# ChargeController.net
KiCad netlist of a schematic drawn in EAGLE
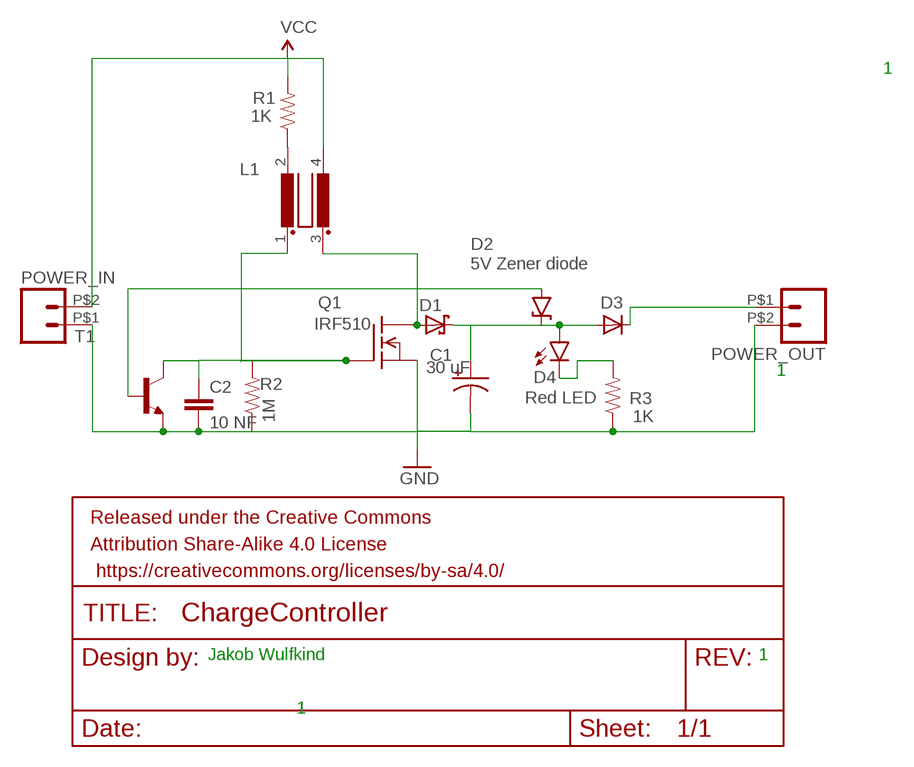
[diagram p0: schematic, sheet 1]

(export (version "E")
  (design (tool "Eeschema 10.0.6"))
  (components
    (comp (ref "C1")
      (value "30 uF")
      (footprint "eagle-import:CPOL-RADIAL-1000UF-25V")
      (libsource (lib "eagle-import") (part "CAP_POLPTH4"))
    )
    (comp (ref "C2")
      (value "10 NF")
      (footprint "eagle-import:CAP-PTH-SMALL-KIT")
      (libsource (lib "eagle-import") (part "0.1UF-50V-20%(PTH)KIT-EZ"))
    )
    (comp (ref "D1")
      (value "SCHOTTKY-DIODEDO201T15")
      (footprint "eagle-import:DO201T15")
      (libsource (lib "eagle-import") (part "SCHOTTKY-DIODEDO201T15"))
    )
    (comp (ref "D2")
      (value "5V Zener diode")
      (footprint "eagle-import:DIODE-ZENER")
      (libsource (lib "eagle-import") (part "DIODE-ZENERPTH"))
    )
    (comp (ref "D3")
      (value "1N5624")
      (footprint "eagle-import:DO201-15")
      (libsource (lib "eagle-import") (part "1N5624"))
    )
    (comp (ref "D4")
      (value "Red LED")
      (footprint "eagle-import:LED3MM")
      (libsource (lib "eagle-import") (part "LED3MM"))
    )
    (comp (ref "FRAME1")
      (value "FRAME-LEDGER")
      (footprint "eagle-import:CREATIVE_COMMONS")
      (libsource (lib "eagle-import") (part "FRAME-LEDGER"))
    )
    (comp (ref "L1")
      (value "R1003XB5")
      (footprint "eagle-import:B5")
      (libsource (lib "eagle-import") (part "R1003XB5"))
    )
    (comp (ref "POWER_IN")
      (value "M02PTH2")
      (footprint "eagle-import:1X02_BIG")
      (libsource (lib "eagle-import") (part "M02PTH2"))
    )
    (comp (ref "POWER_OUT")
      (value "M02PTH2")
      (footprint "eagle-import:1X02_BIG")
      (libsource (lib "eagle-import") (part "M02PTH2"))
    )
    (comp (ref "Q1")
      (value "IRF510")
      (footprint "eagle-import:TO220")
      (libsource (lib "eagle-import") (part "IRF510"))
    )
    (comp (ref "R1")
      (value "1K")
      (footprint "eagle-import:AXIAL-0.4")
      (libsource (lib "eagle-import") (part "RESISTORPTH-1/4W"))
    )
    (comp (ref "R2")
      (value "1M")
      (footprint "eagle-import:AXIAL-0.4")
      (libsource (lib "eagle-import") (part "RESISTORPTH-1/4W"))
    )
    (comp (ref "R3")
      (value "1K")
      (footprint "eagle-import:AXIAL-0.4")
      (libsource (lib "eagle-import") (part "RESISTORPTH-1/4W"))
    )
    (comp (ref "T1")
      (value "-NPN-TO92")
      (footprint "eagle-import:TO92")
      (libsource (lib "eagle-import") (part "-NPN-TO92"))
    )
  )
  (nets
    (net (code "1") (name "GND") (class "Default")
      (node (ref "C1") (pin "-") (pinfunction "-_-") (pintype "passive"))
      (node (ref "C2") (pin "2") (pinfunction "2_2") (pintype "passive"))
      (node (ref "POWER_IN") (pin "P$1") (pinfunction "1_P$1") (pintype "passive"))
      (node (ref "POWER_OUT") (pin "P$2") (pinfunction "2_P$2") (pintype "passive"))
      (node (ref "Q1") (pin "3") (pinfunction "S_3") (pintype "passive"))
      (node (ref "R2") (pin "P$1") (pinfunction "1_P$1") (pintype "passive"))
      (node (ref "R3") (pin "P$1") (pinfunction "1_P$1") (pintype "passive"))
      (node (ref "T1") (pin "1") (pinfunction "E_1") (pintype "passive"))
    )
    (net (code "2") (name "Net-(D2-A)") (class "Default")
      (node (ref "D2") (pin "P$2") (pinfunction "A_P$2") (pintype "passive"))
      (node (ref "T1") (pin "2") (pinfunction "B_2") (pintype "passive"))
    )
    (net (code "3") (name "Net-(D2-C)") (class "Default")
      (node (ref "C1") (pin "+") (pinfunction "+_+") (pintype "passive"))
      (node (ref "D1") (pin "C") (pinfunction "C_C") (pintype "passive"))
      (node (ref "D2") (pin "P$1") (pinfunction "C_P$1") (pintype "passive"))
      (node (ref "D3") (pin "A") (pinfunction "A_A") (pintype "passive"))
      (node (ref "D4") (pin "A") (pinfunction "A_A") (pintype "passive"))
    )
    (net (code "4") (name "Net-(D4-C)") (class "Default")
      (node (ref "D4") (pin "K") (pinfunction "C_K") (pintype "passive"))
      (node (ref "R3") (pin "P$2") (pinfunction "2_P$2") (pintype "passive"))
    )
    (net (code "5") (name "Net-(POWER_OUT-1)") (class "Default")
      (node (ref "D3") (pin "C") (pinfunction "C_C") (pintype "passive"))
      (node (ref "POWER_OUT") (pin "P$1") (pinfunction "1_P$1") (pintype "passive"))
    )
    (net (code "6") (name "Net-(Q1-D)") (class "Default")
      (node (ref "D1") (pin "A") (pinfunction "A_A") (pintype "passive"))
      (node (ref "L1") (pin "3") (pinfunction "3_3") (pintype "passive"))
      (node (ref "Q1") (pin "2") (pinfunction "D_2") (pintype "passive"))
    )
    (net (code "7") (name "Net-(Q1-G)") (class "Default")
      (node (ref "C2") (pin "1") (pinfunction "1_1") (pintype "passive"))
      (node (ref "L1") (pin "1") (pinfunction "1_1") (pintype "passive"))
      (node (ref "Q1") (pin "1") (pinfunction "G_1") (pintype "passive"))
      (node (ref "R2") (pin "P$2") (pinfunction "2_P$2") (pintype "passive"))
      (node (ref "T1") (pin "3") (pinfunction "C_3") (pintype "passive"))
    )
    (net (code "8") (name "Net-(R1-1)") (class "Default")
      (node (ref "L1") (pin "2") (pinfunction "2_2") (pintype "passive"))
      (node (ref "R1") (pin "P$1") (pinfunction "1_P$1") (pintype "passive"))
    )
    (net (code "9") (name "VCC") (class "Default")
      (node (ref "L1") (pin "4") (pinfunction "4_4") (pintype "passive"))
      (node (ref "POWER_IN") (pin "P$2") (pinfunction "2_P$2") (pintype "passive"))
      (node (ref "R1") (pin "P$2") (pinfunction "2_P$2") (pintype "passive"))
    )
  )
)
